# USB_Interface_SCH.net
KiCad netlist of a schematic drawn in Altium Designer
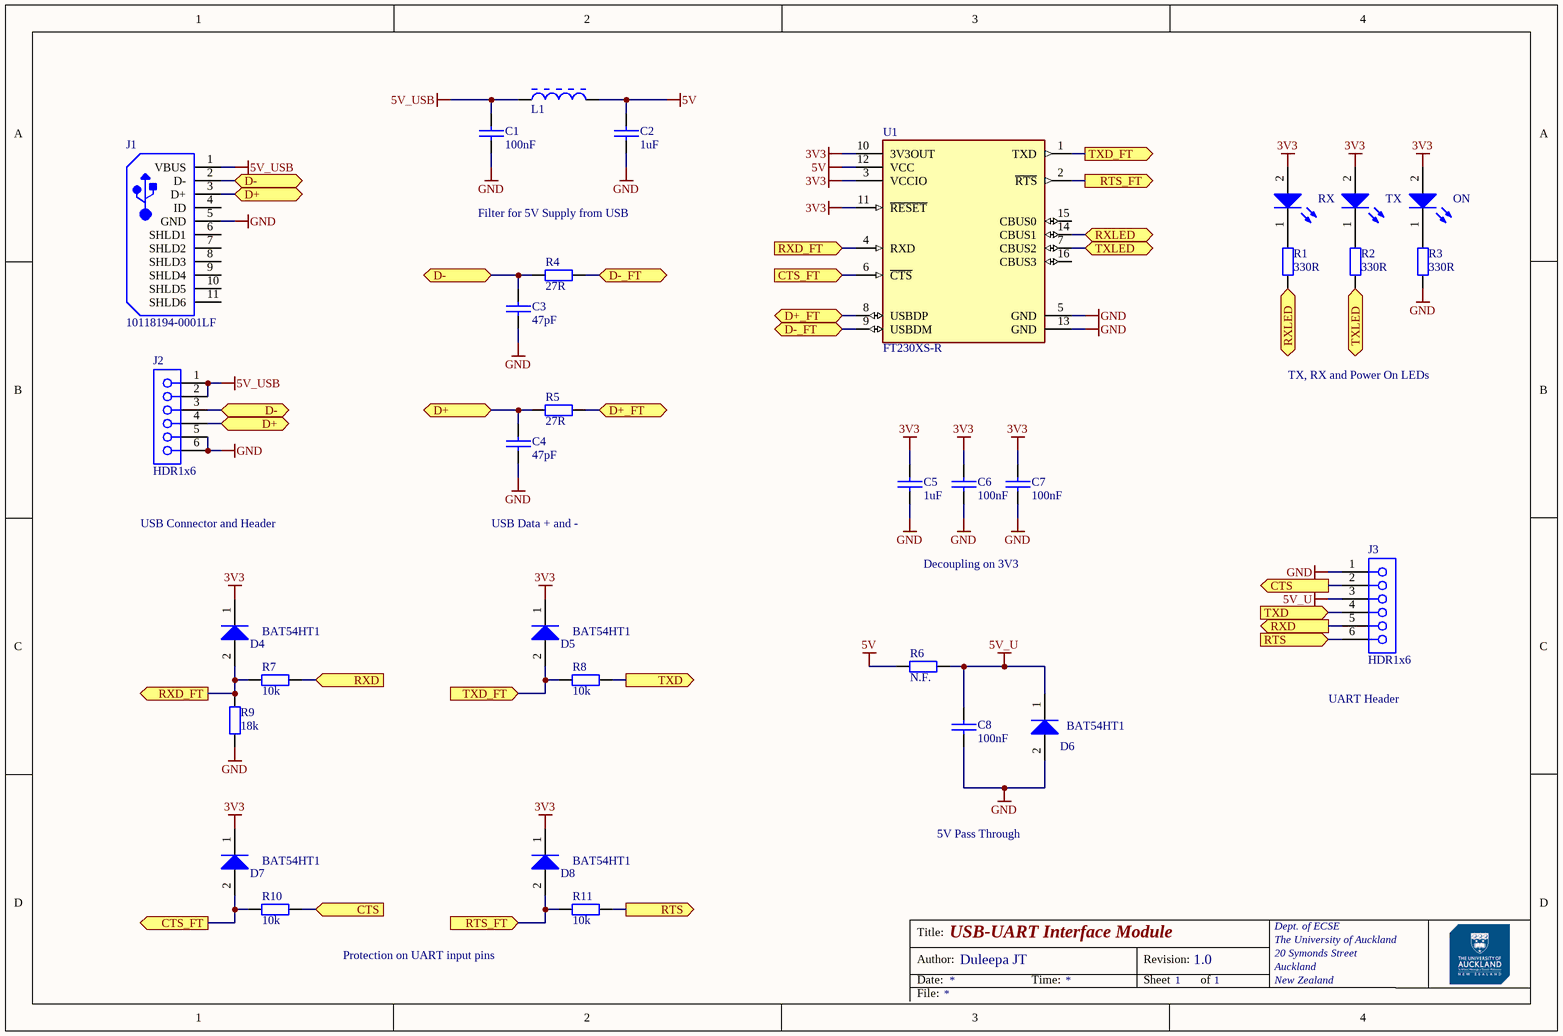
[diagram p0: USB_Interface_SCH.SchDoc]

(export (version "E")
  (design (tool "Eeschema 10.0.6"))
  (components
    (comp (ref "C1")
      (value "100nF")
      (footprint "C0805")
      (description "CCAP0805")
      (fields (field (name "LCSC PART NUMBER") "C62912") (field (name "JLC PART NUMBER") "CL21B104JBCNNNC"))
      (libsource (lib "CommonDevices_V1") (part "CCAP0805"))
    )
    (comp (ref "C2")
      (value "1uF")
      (footprint "C0805")
      (description "CCAP0805")
      (fields (field (name "LCSC PART NUMBER") "C28323") (field (name "JLC PART") "CL21B105KBFNNNE"))
      (libsource (lib "CommonDevices_V1") (part "CCAP0805"))
    )
    (comp (ref "C3")
      (value "47pF")
      (footprint "C0805")
      (description "CCAP0805")
      (fields (field (name "LCSC PART NUMBER") "C14857") (field (name "JLC PART") "CL21C470JBANNNC"))
      (libsource (lib "CommonDevices_V1") (part "CCAP0805"))
    )
    (comp (ref "C4")
      (value "47pF")
      (footprint "C0805")
      (description "CCAP0805")
      (fields (field (name "LCSC PART NUMBER") "C14857") (field (name "JLC PART") "CL21C470JBANNNC"))
      (libsource (lib "CommonDevices_V1") (part "CCAP0805"))
    )
    (comp (ref "C5")
      (value "1uF")
      (footprint "C0805")
      (description "CCAP0805")
      (fields (field (name "LCSC PART NUMBER") "C28323") (field (name "JLC PART NUMBER") "CL21B105KBFNNNE"))
      (libsource (lib "CommonDevices_V1") (part "CCAP0805"))
    )
    (comp (ref "C6")
      (value "100nF")
      (footprint "C0805")
      (description "CCAP0805")
      (fields (field (name "LCSC PART NUMBER") "C62912") (field (name "JLC PART NUMBER") "CL21B104JBCNNNC"))
      (libsource (lib "CommonDevices_V1") (part "CCAP0805"))
    )
    (comp (ref "C7")
      (value "100nF")
      (footprint "C0805")
      (description "CCAP0805")
      (fields (field (name "LCSC PART NUMBER") "C62912") (field (name "JLC PART NUMBER") "CL21B104JBCNNNC"))
      (libsource (lib "CommonDevices_V1") (part "CCAP0805"))
    )
    (comp (ref "C8")
      (value "100nF")
      (footprint "C0805")
      (description "CCAP0805")
      (fields (field (name "LCSC PART NUMBER") "C62912") (field (name "JLC PART NUMBER") "CL21B104JBCNNNC"))
      (libsource (lib "CommonDevices_V1") (part "CCAP0805"))
    )
    (comp (ref "D4")
      (value "BAT54HT1")
      (footprint "ONSC-SOD-323-2-477-02_V")
      (description "DIODE SCHOTTKY 30V 200MA SOD323")
      (fields (field (name "LCSC PART NUMBER") "C21107"))
      (libsource (lib "ECSE@UoA") (part "ONSC-D-K1A2-2"))
    )
    (comp (ref "D5")
      (value "BAT54HT1")
      (footprint "ONSC-SOD-323-2-477-02_V")
      (description "DIODE SCHOTTKY 30V 200MA SOD323")
      (fields (field (name "LCSC PART NUMBER") "C21107"))
      (libsource (lib "ECSE@UoA") (part "ONSC-D-K1A2-2"))
    )
    (comp (ref "D6")
      (value "BAT54HT1")
      (footprint "ONSC-SOD-323-2-477-02_V")
      (description "DIODE SCHOTTKY 30V 200MA SOD323")
      (fields (field (name "LCSC PART NUMBER") "C21107"))
      (libsource (lib "ECSE@UoA") (part "ONSC-D-K1A2-2"))
    )
    (comp (ref "D7")
      (value "BAT54HT1")
      (footprint "ONSC-SOD-323-2-477-02_V")
      (description "DIODE SCHOTTKY 30V 200MA SOD323")
      (fields (field (name "LCSC PART NUMBER") "C21107"))
      (libsource (lib "ECSE@UoA") (part "ONSC-D-K1A2-2"))
    )
    (comp (ref "D8")
      (value "BAT54HT1")
      (footprint "ONSC-SOD-323-2-477-02_V")
      (description "DIODE SCHOTTKY 30V 200MA SOD323")
      (fields (field (name "LCSC PART NUMBER") "C21107"))
      (libsource (lib "ECSE@UoA") (part "ONSC-D-K1A2-2"))
    )
    (comp (ref "J1")
      (value "10118194-0001LF")
      (footprint "FCI-10118194-0001LF-5_V")
      (description "CONN USB MICRO B RECPT SMT R/A")
      (libsource (lib "ECSE@UoA") (part "USB-5-6SHLD"))
    )
    (comp (ref "J2")
      (value "HDR1x6")
      (footprint "SMTC-SSW-106-02-X-S")
      (description "CONN RCPT 6POS 0.1 TIN PCB")
      (libsource (lib "ECSE@UoA") (part "SMTC-SSW-106-02-X-S-X"))
    )
    (comp (ref "J3")
      (value "HDR1x6")
      (footprint "SMTC-SSW-106-02-X-S")
      (description "CONN RCPT 6POS 0.1 TIN PCB")
      (libsource (lib "ECSE@UoA") (part "SMTC-SSW-106-02-X-S-X"))
    )
    (comp (ref "L1")
      (value "FBMH3225HM102NT")
      (footprint "TAYO-3225-2_V")
      (description "TAIYO YUDEN         FBMH3225HM102NT            Ferrite Case Style:1210 [3225 Metric]")
      (fields (field (name "LCSC PART NUMBER") "C124093"))
      (libsource (lib "ECSE@UoA") (part "IND-FB-2"))
    )
    (comp (ref "ON")
      (value "LGR971-KN-1")
      (footprint "FP-LG_R971-MFG")
      (description "LED Uni-Color Green 572nm 2-Pin SMD T/R")
      (fields (field (name "LCSC PART NUMBER") "C2297"))
      (libsource (lib "ECSE@UoA") (part "8706943c75ba83719d021d2fdc84c58"))
    )
    (comp (ref "R1")
      (value "330R")
      (footprint "R0805")
      (description "RES0805")
      (fields (field (name "LCSC PART NUMBER") "C17630"))
      (libsource (lib "CommonDevices_V1") (part "RES0805"))
    )
    (comp (ref "R2")
      (value "330R")
      (footprint "R0805")
      (description "RES0805")
      (fields (field (name "LCSC PART NUMBER") "C17630"))
      (libsource (lib "CommonDevices_V1") (part "RES0805"))
    )
    (comp (ref "R3")
      (value "330R")
      (footprint "R0805")
      (description "RES0805")
      (fields (field (name "LCSC PART NUMBER") "C17630"))
      (libsource (lib "CommonDevices_V1") (part "RES0805"))
    )
    (comp (ref "R4")
      (value "27R")
      (footprint "R0805")
      (description "RES0805")
      (fields (field (name "LCSC PART NUMBER") "C17594"))
      (libsource (lib "") (part "RES0805_2"))
    )
    (comp (ref "R5")
      (value "27R")
      (footprint "R0805")
      (description "RES0805")
      (fields (field (name "LCSC PART NUMBER") "C17594"))
      (libsource (lib "") (part "RES0805_2"))
    )
    (comp (ref "R6")
      (value "N.F.")
      (footprint "R0805")
      (description "RES0805")
      (libsource (lib "") (part "RES0805_1"))
    )
    (comp (ref "R7")
      (value "10k")
      (footprint "R0805")
      (description "RES0805")
      (fields (field (name "LCSC PART NUMBER") "C17414"))
      (libsource (lib "") (part "RES0805_1"))
    )
    (comp (ref "R8")
      (value "10k")
      (footprint "R0805")
      (description "RES0805")
      (fields (field (name "LCSC PART NUMBER") "C17414"))
      (libsource (lib "") (part "RES0805_1"))
    )
    (comp (ref "R9")
      (value "18k")
      (footprint "R0805")
      (description "RES0805")
      (fields (field (name "LCSC PART NUMBER") "C17506"))
      (libsource (lib "") (part "RES0805_3"))
    )
    (comp (ref "R10")
      (value "10k")
      (footprint "R0805")
      (description "RES0805")
      (fields (field (name "LCSC PART NUMBER") "C17414"))
      (libsource (lib "") (part "RES0805_1"))
    )
    (comp (ref "R11")
      (value "10k")
      (footprint "R0805")
      (description "RES0805")
      (fields (field (name "LCSC PART NUMBER") "C17414"))
      (libsource (lib "") (part "RES0805_1"))
    )
    (comp (ref "RX")
      (value "LGR971-KN-1")
      (footprint "FP-LG_R971-MFG")
      (description "LED Uni-Color Green 572nm 2-Pin SMD T/R")
      (fields (field (name "LCSC PART NUMBER") "C2297"))
      (libsource (lib "ECSE@UoA") (part "8706943c75ba83719d021d2fdc84c58"))
    )
    (comp (ref "TX")
      (value "LSR976-NR-1")
      (footprint "FP-LS_R976-MFG")
      (description "LED RED DIFFUSED 0805 SMD")
      (fields (field (name "LCSC PART NUMBER") "C84256"))
      (libsource (lib "ECSE@UoA") (part "8706943c75ba83719d021d2fdc84c58"))
    )
    (comp (ref "U1")
      (value "FT230XS-R")
      (footprint "FP-SSOP-16-IPC_C")
      (description "USB-to-UART 1-CH 512byte FIFO 5V 16-Pin SSOP T/R")
      (fields (field (name "LCSC PART NUMBER") "C69082"))
      (libsource (lib "ECSE@UoA") (part "33f179d67b5e33a3acba2e4c59411a5"))
    )
  )
  (nets
    (net (code "1") (name "/CTS") (class "Default")
      (node (ref "J3") (pin "2") (pinfunction "2_2") (pintype "passive"))
      (node (ref "R10") (pin "2") (pinfunction "2_2") (pintype "passive"))
    )
    (net (code "2") (name "/CTS_FT") (class "Default")
      (node (ref "D7") (pin "2") (pinfunction "A_2") (pintype "passive"))
      (node (ref "R10") (pin "1") (pinfunction "1_1") (pintype "passive"))
      (node (ref "U1") (pin "6") (pinfunction "~{CTS}_6") (pintype "input"))
    )
    (net (code "3") (name "/D+") (class "Default")
      (node (ref "C4") (pin "2") (pinfunction "2_2") (pintype "passive"))
      (node (ref "J1") (pin "3") (pinfunction "D+_3") (pintype "passive"))
      (node (ref "J2") (pin "4") (pinfunction "4_4") (pintype "passive"))
      (node (ref "R5") (pin "1") (pinfunction "1_1") (pintype "passive"))
    )
    (net (code "4") (name "/D+_FT") (class "Default")
      (node (ref "R5") (pin "2") (pinfunction "2_2") (pintype "passive"))
      (node (ref "U1") (pin "8") (pinfunction "USBDP_8") (pintype "bidirectional"))
    )
    (net (code "5") (name "/D-") (class "Default")
      (node (ref "C3") (pin "2") (pinfunction "2_2") (pintype "passive"))
      (node (ref "J1") (pin "2") (pinfunction "D-_2") (pintype "passive"))
      (node (ref "J2") (pin "3") (pinfunction "3_3") (pintype "passive"))
      (node (ref "R4") (pin "1") (pinfunction "1_1") (pintype "passive"))
    )
    (net (code "6") (name "/D-_FT") (class "Default")
      (node (ref "R4") (pin "2") (pinfunction "2_2") (pintype "passive"))
      (node (ref "U1") (pin "9") (pinfunction "USBDM_9") (pintype "bidirectional"))
    )
    (net (code "7") (name "/RTS") (class "Default")
      (node (ref "J3") (pin "6") (pinfunction "6_6") (pintype "passive"))
      (node (ref "R11") (pin "2") (pinfunction "2_2") (pintype "passive"))
    )
    (net (code "8") (name "/RTS_FT") (class "Default")
      (node (ref "D8") (pin "2") (pinfunction "A_2") (pintype "passive"))
      (node (ref "R11") (pin "1") (pinfunction "1_1") (pintype "passive"))
      (node (ref "U1") (pin "2") (pinfunction "~{RTS}_2") (pintype "output"))
    )
    (net (code "9") (name "/RXD") (class "Default")
      (node (ref "J3") (pin "5") (pinfunction "5_5") (pintype "passive"))
      (node (ref "R7") (pin "2") (pinfunction "2_2") (pintype "passive"))
    )
    (net (code "10") (name "/RXD_FT") (class "Default")
      (node (ref "D4") (pin "2") (pinfunction "A_2") (pintype "passive"))
      (node (ref "R7") (pin "1") (pinfunction "1_1") (pintype "passive"))
      (node (ref "R9") (pin "1") (pinfunction "1_1") (pintype "passive"))
      (node (ref "U1") (pin "4") (pinfunction "RXD_4") (pintype "input"))
    )
    (net (code "11") (name "/RXLED") (class "Default")
      (node (ref "R1") (pin "2") (pinfunction "2_2") (pintype "passive"))
      (node (ref "U1") (pin "14") (pinfunction "CBUS1_14") (pintype "bidirectional"))
    )
    (net (code "12") (name "/TXD") (class "Default")
      (node (ref "J3") (pin "4") (pinfunction "4_4") (pintype "passive"))
      (node (ref "R8") (pin "2") (pinfunction "2_2") (pintype "passive"))
    )
    (net (code "13") (name "/TXD_FT") (class "Default")
      (node (ref "D5") (pin "2") (pinfunction "A_2") (pintype "passive"))
      (node (ref "R8") (pin "1") (pinfunction "1_1") (pintype "passive"))
      (node (ref "U1") (pin "1") (pinfunction "TXD_1") (pintype "output"))
    )
    (net (code "14") (name "/TXLED") (class "Default")
      (node (ref "R2") (pin "2") (pinfunction "2_2") (pintype "passive"))
      (node (ref "U1") (pin "7") (pinfunction "CBUS2_7") (pintype "bidirectional"))
    )
    (net (code "15") (name "3V3") (class "Default")
      (node (ref "C5") (pin "1") (pinfunction "1_1") (pintype "passive"))
      (node (ref "C6") (pin "1") (pinfunction "1_1") (pintype "passive"))
      (node (ref "C7") (pin "2") (pinfunction "2_2") (pintype "passive"))
      (node (ref "D4") (pin "1") (pinfunction "K_1") (pintype "passive"))
      (node (ref "D5") (pin "1") (pinfunction "K_1") (pintype "passive"))
      (node (ref "D7") (pin "1") (pinfunction "K_1") (pintype "passive"))
      (node (ref "D8") (pin "1") (pinfunction "K_1") (pintype "passive"))
      (node (ref "ON") (pin "2") (pinfunction "A_2") (pintype "passive"))
      (node (ref "RX") (pin "2") (pinfunction "A_2") (pintype "passive"))
      (node (ref "TX") (pin "2") (pinfunction "A_2") (pintype "passive"))
      (node (ref "U1") (pin "10") (pinfunction "3V3OUT_10") (pintype "power_in"))
      (node (ref "U1") (pin "11") (pinfunction "~{RESET}_11") (pintype "input"))
      (node (ref "U1") (pin "3") (pinfunction "VCCIO_3") (pintype "power_in"))
    )
    (net (code "16") (name "5V") (class "Default")
      (node (ref "C2") (pin "1") (pinfunction "1_1") (pintype "passive"))
      (node (ref "L1") (pin "2") (pinfunction "2_2") (pintype "passive"))
      (node (ref "R6") (pin "1") (pinfunction "1_1") (pintype "passive"))
      (node (ref "U1") (pin "12") (pinfunction "VCC_12") (pintype "power_in"))
    )
    (net (code "17") (name "5V_U") (class "Default")
      (node (ref "C8") (pin "2") (pinfunction "2_2") (pintype "passive"))
      (node (ref "D6") (pin "1") (pinfunction "K_1") (pintype "passive"))
      (node (ref "J3") (pin "3") (pinfunction "3_3") (pintype "passive"))
      (node (ref "R6") (pin "2") (pinfunction "2_2") (pintype "passive"))
    )
    (net (code "18") (name "5V_USB") (class "Default")
      (node (ref "C1") (pin "1") (pinfunction "1_1") (pintype "passive"))
      (node (ref "J1") (pin "1") (pinfunction "VBUS_1") (pintype "passive"))
      (node (ref "J2") (pin "1") (pinfunction "1_1") (pintype "passive"))
      (node (ref "J2") (pin "2") (pinfunction "2_2") (pintype "passive"))
      (node (ref "L1") (pin "1") (pinfunction "1_1") (pintype "passive"))
    )
    (net (code "19") (name "GND") (class "Default")
      (node (ref "C1") (pin "2") (pinfunction "2_2") (pintype "passive"))
      (node (ref "C2") (pin "2") (pinfunction "2_2") (pintype "passive"))
      (node (ref "C3") (pin "1") (pinfunction "1_1") (pintype "passive"))
      (node (ref "C4") (pin "1") (pinfunction "1_1") (pintype "passive"))
      (node (ref "C5") (pin "2") (pinfunction "2_2") (pintype "passive"))
      (node (ref "C6") (pin "2") (pinfunction "2_2") (pintype "passive"))
      (node (ref "C7") (pin "1") (pinfunction "1_1") (pintype "passive"))
      (node (ref "C8") (pin "1") (pinfunction "1_1") (pintype "passive"))
      (node (ref "D6") (pin "2") (pinfunction "A_2") (pintype "passive"))
      (node (ref "J1") (pin "5") (pinfunction "GND_5") (pintype "passive"))
      (node (ref "J2") (pin "5") (pinfunction "5_5") (pintype "passive"))
      (node (ref "J2") (pin "6") (pinfunction "6_6") (pintype "passive"))
      (node (ref "J3") (pin "1") (pinfunction "1_1") (pintype "passive"))
      (node (ref "R3") (pin "2") (pinfunction "2_2") (pintype "passive"))
      (node (ref "R9") (pin "2") (pinfunction "2_2") (pintype "passive"))
      (node (ref "U1") (pin "13") (pinfunction "GND_13") (pintype "power_in"))
      (node (ref "U1") (pin "5") (pinfunction "GND_5") (pintype "power_in"))
    )
    (net (code "20") (name "Net-(ON-C)") (class "Default")
      (node (ref "ON") (pin "1") (pinfunction "C_1") (pintype "passive"))
      (node (ref "R3") (pin "1") (pinfunction "1_1") (pintype "passive"))
    )
    (net (code "21") (name "Net-(RX-C)") (class "Default")
      (node (ref "R1") (pin "1") (pinfunction "1_1") (pintype "passive"))
      (node (ref "RX") (pin "1") (pinfunction "C_1") (pintype "passive"))
    )
    (net (code "22") (name "Net-(TX-C)") (class "Default")
      (node (ref "R2") (pin "1") (pinfunction "1_1") (pintype "passive"))
      (node (ref "TX") (pin "1") (pinfunction "C_1") (pintype "passive"))
    )
    (net (code "23") (name "unconnected-(J1-ID-Pad4)") (class "Default")
      (node (ref "J1") (pin "4") (pinfunction "ID_4") (pintype "passive"))
    )
    (net (code "24") (name "unconnected-(J1-SHLD1-Pad6)") (class "Default")
      (node (ref "J1") (pin "6") (pinfunction "SHLD1_6") (pintype "passive"))
    )
    (net (code "25") (name "unconnected-(J1-SHLD2-Pad7)") (class "Default")
      (node (ref "J1") (pin "7") (pinfunction "SHLD2_7") (pintype "passive"))
    )
    (net (code "26") (name "unconnected-(J1-SHLD3-Pad8)") (class "Default")
      (node (ref "J1") (pin "8") (pinfunction "SHLD3_8") (pintype "passive"))
    )
    (net (code "27") (name "unconnected-(J1-SHLD4-Pad9)") (class "Default")
      (node (ref "J1") (pin "9") (pinfunction "SHLD4_9") (pintype "passive"))
    )
    (net (code "28") (name "unconnected-(J1-SHLD5-Pad10)") (class "Default")
      (node (ref "J1") (pin "10") (pinfunction "SHLD5_10") (pintype "passive"))
    )
    (net (code "29") (name "unconnected-(J1-SHLD6-Pad11)") (class "Default")
      (node (ref "J1") (pin "11") (pinfunction "SHLD6_11") (pintype "passive"))
    )
    (net (code "30") (name "unconnected-(U1-CBUS0-Pad15)") (class "Default")
      (node (ref "U1") (pin "15") (pinfunction "CBUS0_15") (pintype "bidirectional"))
    )
    (net (code "31") (name "unconnected-(U1-CBUS3-Pad16)") (class "Default")
      (node (ref "U1") (pin "16") (pinfunction "CBUS3_16") (pintype "bidirectional"))
    )
  )
)
